# mainboard.net
KiCad netlist of a schematic drawn in EAGLE
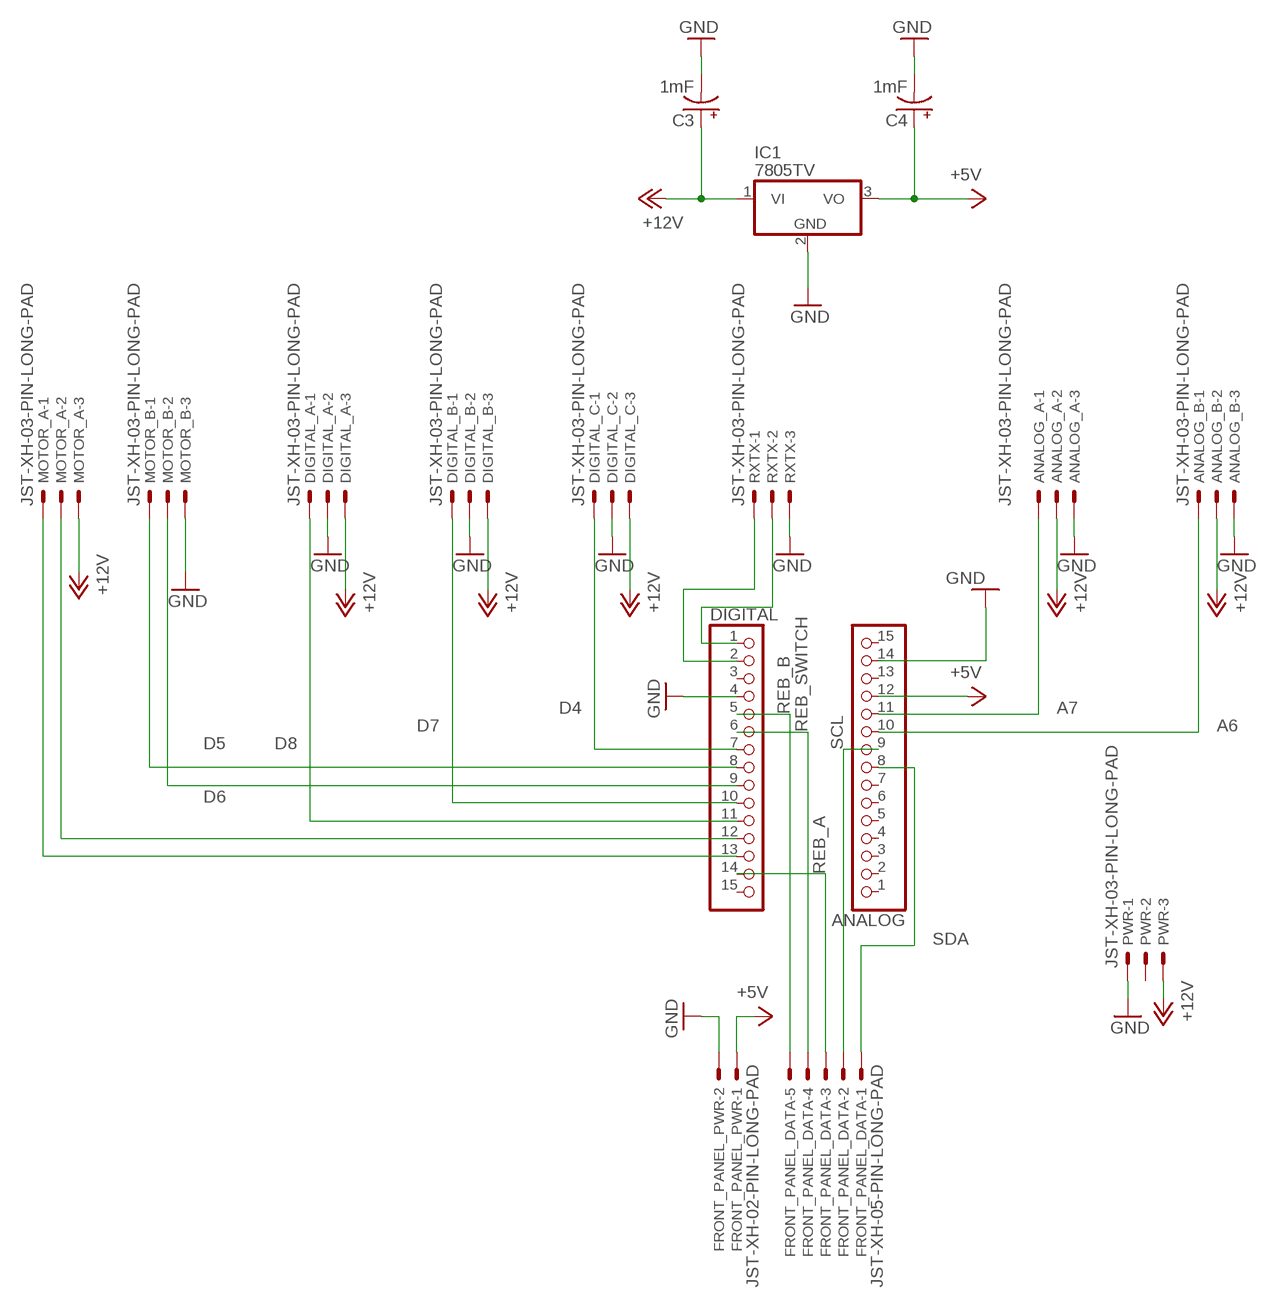
[diagram p0: schematic, sheet 1]

(export (version "E")
  (design (tool "Eeschema 10.0.6"))
  (components
    (comp (ref "ANALOG")
      (value "PINHD-1X15")
      (footprint "eagle-import:1X15")
      (libsource (lib "eagle-import") (part "PINHD-1X15"))
    )
    (comp (ref "ANALOG_A")
      (value "JST-XH-03-PIN-LONG-PAD")
      (footprint "eagle-import:JST-XH-03-PACKAGE-LONG-PAD")
      (libsource (lib "eagle-import") (part "JST-XH-03-PIN-LONG-PAD"))
    )
    (comp (ref "ANALOG_B")
      (value "JST-XH-03-PIN-LONG-PAD")
      (footprint "eagle-import:JST-XH-03-PACKAGE-LONG-PAD")
      (libsource (lib "eagle-import") (part "JST-XH-03-PIN-LONG-PAD"))
    )
    (comp (ref "C3")
      (value "1mF")
      (footprint "eagle-import:CPOL-RADIAL-5MM-10MM")
      (libsource (lib "eagle-import") (part "1000UF-RADIAL-5MM-25V-20%"))
    )
    (comp (ref "C4")
      (value "1mF")
      (footprint "eagle-import:CPOL-RADIAL-5MM-10MM")
      (libsource (lib "eagle-import") (part "1000UF-RADIAL-5MM-25V-20%"))
    )
    (comp (ref "DIGITAL")
      (value "PINHD-1X15")
      (footprint "eagle-import:1X15")
      (libsource (lib "eagle-import") (part "PINHD-1X15"))
    )
    (comp (ref "DIGITAL_A")
      (value "JST-XH-03-PIN-LONG-PAD")
      (footprint "eagle-import:JST-XH-03-PACKAGE-LONG-PAD")
      (libsource (lib "eagle-import") (part "JST-XH-03-PIN-LONG-PAD"))
    )
    (comp (ref "DIGITAL_B")
      (value "JST-XH-03-PIN-LONG-PAD")
      (footprint "eagle-import:JST-XH-03-PACKAGE-LONG-PAD")
      (libsource (lib "eagle-import") (part "JST-XH-03-PIN-LONG-PAD"))
    )
    (comp (ref "DIGITAL_C")
      (value "JST-XH-03-PIN-LONG-PAD")
      (footprint "eagle-import:JST-XH-03-PACKAGE-LONG-PAD")
      (libsource (lib "eagle-import") (part "JST-XH-03-PIN-LONG-PAD"))
    )
    (comp (ref "FRONT_PANEL_DATA")
      (value "JST-XH-05-PIN-LONG-PAD")
      (footprint "eagle-import:JST-XH-05-PACKAGE-LONG-PAD")
      (libsource (lib "eagle-import") (part "JST-XH-05-PIN-LONG-PAD"))
    )
    (comp (ref "FRONT_PANEL_PWR")
      (value "JST-XH-02-PIN-LONG-PAD")
      (footprint "eagle-import:JST-XH-02-PACKAGE-LONG-PAD")
      (libsource (lib "eagle-import") (part "JST-XH-02-PIN-LONG-PAD"))
    )
    (comp (ref "IC1")
      (value "7805TV")
      (footprint "eagle-import:TO220V")
      (libsource (lib "eagle-import") (part "78TV05"))
    )
    (comp (ref "MOTOR_A")
      (value "JST-XH-03-PIN-LONG-PAD")
      (footprint "eagle-import:JST-XH-03-PACKAGE-LONG-PAD")
      (libsource (lib "eagle-import") (part "JST-XH-03-PIN-LONG-PAD"))
    )
    (comp (ref "MOTOR_B")
      (value "JST-XH-03-PIN-LONG-PAD")
      (footprint "eagle-import:JST-XH-03-PACKAGE-LONG-PAD")
      (libsource (lib "eagle-import") (part "JST-XH-03-PIN-LONG-PAD"))
    )
    (comp (ref "PWR")
      (value "JST-XH-03-PIN-LONG-PAD")
      (footprint "eagle-import:JST-XH-03-PACKAGE-LONG-PAD")
      (libsource (lib "eagle-import") (part "JST-XH-03-PIN-LONG-PAD"))
    )
    (comp (ref "RXTX")
      (value "JST-XH-03-PIN-LONG-PAD")
      (footprint "eagle-import:JST-XH-03-PACKAGE-LONG-PAD")
      (libsource (lib "eagle-import") (part "JST-XH-03-PIN-LONG-PAD"))
    )
  )
  (nets
    (net (code "1") (name "+5V") (class "Default")
      (node (ref "ANALOG") (pin "12") (pinfunction "12_12") (pintype "passive"))
      (node (ref "C4") (pin "+") (pinfunction "+_+") (pintype "passive"))
      (node (ref "FRONT_PANEL_PWR") (pin "1") (pinfunction "S_1") (pintype "passive"))
      (node (ref "IC1") (pin "3") (pinfunction "VO_3") (pintype "passive"))
    )
    (net (code "2") (name "+12V") (class "Default")
      (node (ref "ANALOG_A") (pin "2") (pinfunction "S_2") (pintype "passive"))
      (node (ref "ANALOG_B") (pin "2") (pinfunction "S_2") (pintype "passive"))
      (node (ref "C3") (pin "+") (pinfunction "+_+") (pintype "passive"))
      (node (ref "DIGITAL_A") (pin "3") (pinfunction "S_3") (pintype "passive"))
      (node (ref "DIGITAL_B") (pin "3") (pinfunction "S_3") (pintype "passive"))
      (node (ref "DIGITAL_C") (pin "3") (pinfunction "S_3") (pintype "passive"))
      (node (ref "IC1") (pin "1") (pinfunction "VI_1") (pintype "input"))
      (node (ref "MOTOR_A") (pin "3") (pinfunction "S_3") (pintype "passive"))
      (node (ref "PWR") (pin "3") (pinfunction "S_3") (pintype "passive"))
    )
    (net (code "3") (name "/A6") (class "Default")
      (node (ref "ANALOG") (pin "10") (pinfunction "10_10") (pintype "passive"))
      (node (ref "ANALOG_B") (pin "1") (pinfunction "S_1") (pintype "passive"))
    )
    (net (code "4") (name "/A7") (class "Default")
      (node (ref "ANALOG") (pin "11") (pinfunction "11_11") (pintype "passive"))
      (node (ref "ANALOG_A") (pin "1") (pinfunction "S_1") (pintype "passive"))
    )
    (net (code "5") (name "/D4") (class "Default")
      (node (ref "DIGITAL") (pin "7") (pinfunction "7_7") (pintype "passive"))
      (node (ref "DIGITAL_C") (pin "1") (pinfunction "S_1") (pintype "passive"))
    )
    (net (code "6") (name "/D5") (class "Default")
      (node (ref "DIGITAL") (pin "8") (pinfunction "8_8") (pintype "passive"))
      (node (ref "MOTOR_B") (pin "1") (pinfunction "S_1") (pintype "passive"))
    )
    (net (code "7") (name "/D6") (class "Default")
      (node (ref "DIGITAL") (pin "9") (pinfunction "9_9") (pintype "passive"))
      (node (ref "MOTOR_B") (pin "2") (pinfunction "S_2") (pintype "passive"))
    )
    (net (code "8") (name "/D7") (class "Default")
      (node (ref "DIGITAL") (pin "10") (pinfunction "10_10") (pintype "passive"))
      (node (ref "DIGITAL_B") (pin "1") (pinfunction "S_1") (pintype "passive"))
    )
    (net (code "9") (name "/D8") (class "Default")
      (node (ref "DIGITAL") (pin "11") (pinfunction "11_11") (pintype "passive"))
      (node (ref "DIGITAL_A") (pin "1") (pinfunction "S_1") (pintype "passive"))
    )
    (net (code "10") (name "/REB_A") (class "Default")
      (node (ref "DIGITAL") (pin "14") (pinfunction "14_14") (pintype "passive"))
      (node (ref "FRONT_PANEL_DATA") (pin "3") (pinfunction "S_3") (pintype "passive"))
    )
    (net (code "11") (name "/REB_B") (class "Default")
      (node (ref "DIGITAL") (pin "5") (pinfunction "5_5") (pintype "passive"))
      (node (ref "FRONT_PANEL_DATA") (pin "5") (pinfunction "S_5") (pintype "passive"))
    )
    (net (code "12") (name "/REB_SWITCH") (class "Default")
      (node (ref "DIGITAL") (pin "6") (pinfunction "6_6") (pintype "passive"))
      (node (ref "FRONT_PANEL_DATA") (pin "4") (pinfunction "S_4") (pintype "passive"))
    )
    (net (code "13") (name "/SCL") (class "Default")
      (node (ref "ANALOG") (pin "9") (pinfunction "9_9") (pintype "passive"))
      (node (ref "FRONT_PANEL_DATA") (pin "2") (pinfunction "S_2") (pintype "passive"))
    )
    (net (code "14") (name "/SDA") (class "Default")
      (node (ref "ANALOG") (pin "8") (pinfunction "8_8") (pintype "passive"))
      (node (ref "FRONT_PANEL_DATA") (pin "1") (pinfunction "S_1") (pintype "passive"))
    )
    (net (code "15") (name "GND") (class "Default")
      (node (ref "ANALOG") (pin "14") (pinfunction "14_14") (pintype "passive"))
      (node (ref "ANALOG_A") (pin "3") (pinfunction "S_3") (pintype "passive"))
      (node (ref "ANALOG_B") (pin "3") (pinfunction "S_3") (pintype "passive"))
      (node (ref "C3") (pin "-") (pinfunction "-_-") (pintype "passive"))
      (node (ref "C4") (pin "-") (pinfunction "-_-") (pintype "passive"))
      (node (ref "DIGITAL") (pin "4") (pinfunction "4_4") (pintype "passive"))
      (node (ref "DIGITAL_A") (pin "2") (pinfunction "S_2") (pintype "passive"))
      (node (ref "DIGITAL_B") (pin "2") (pinfunction "S_2") (pintype "passive"))
      (node (ref "DIGITAL_C") (pin "2") (pinfunction "S_2") (pintype "passive"))
      (node (ref "FRONT_PANEL_PWR") (pin "2") (pinfunction "S_2") (pintype "passive"))
      (node (ref "IC1") (pin "2") (pinfunction "GND_2") (pintype "passive"))
      (node (ref "MOTOR_B") (pin "3") (pinfunction "S_3") (pintype "passive"))
      (node (ref "PWR") (pin "1") (pinfunction "S_1") (pintype "passive"))
      (node (ref "RXTX") (pin "3") (pinfunction "S_3") (pintype "passive"))
    )
    (net (code "16") (name "Net-(MOTOR_AA-S)") (class "Default")
      (node (ref "DIGITAL") (pin "13") (pinfunction "13_13") (pintype "passive"))
      (node (ref "MOTOR_A") (pin "1") (pinfunction "S_1") (pintype "passive"))
    )
    (net (code "17") (name "Net-(MOTOR_AB-S)") (class "Default")
      (node (ref "DIGITAL") (pin "12") (pinfunction "12_12") (pintype "passive"))
      (node (ref "MOTOR_A") (pin "2") (pinfunction "S_2") (pintype "passive"))
    )
    (net (code "18") (name "Net-(RXTXA-S)") (class "Default")
      (node (ref "DIGITAL") (pin "2") (pinfunction "2_2") (pintype "passive"))
      (node (ref "RXTX") (pin "1") (pinfunction "S_1") (pintype "passive"))
    )
    (net (code "19") (name "Net-(RXTXB-S)") (class "Default")
      (node (ref "DIGITAL") (pin "1") (pinfunction "1_1") (pintype "passive"))
      (node (ref "RXTX") (pin "2") (pinfunction "S_2") (pintype "passive"))
    )
    (net (code "20") (name "unconnected-(ANALOG-Pad1)") (class "Default")
      (node (ref "ANALOG") (pin "1") (pinfunction "1_1") (pintype "passive"))
    )
    (net (code "21") (name "unconnected-(ANALOG-Pad2)") (class "Default")
      (node (ref "ANALOG") (pin "2") (pinfunction "2_2") (pintype "passive"))
    )
    (net (code "22") (name "unconnected-(ANALOG-Pad3)") (class "Default")
      (node (ref "ANALOG") (pin "3") (pinfunction "3_3") (pintype "passive"))
    )
    (net (code "23") (name "unconnected-(ANALOG-Pad4)") (class "Default")
      (node (ref "ANALOG") (pin "4") (pinfunction "4_4") (pintype "passive"))
    )
    (net (code "24") (name "unconnected-(ANALOG-Pad5)") (class "Default")
      (node (ref "ANALOG") (pin "5") (pinfunction "5_5") (pintype "passive"))
    )
    (net (code "25") (name "unconnected-(ANALOG-Pad6)") (class "Default")
      (node (ref "ANALOG") (pin "6") (pinfunction "6_6") (pintype "passive"))
    )
    (net (code "26") (name "unconnected-(ANALOG-Pad7)") (class "Default")
      (node (ref "ANALOG") (pin "7") (pinfunction "7_7") (pintype "passive"))
    )
    (net (code "27") (name "unconnected-(ANALOG-Pad13)") (class "Default")
      (node (ref "ANALOG") (pin "13") (pinfunction "13_13") (pintype "passive"))
    )
    (net (code "28") (name "unconnected-(ANALOG-Pad15)") (class "Default")
      (node (ref "ANALOG") (pin "15") (pinfunction "15_15") (pintype "passive"))
    )
    (net (code "29") (name "unconnected-(DIGITAL-Pad3)") (class "Default")
      (node (ref "DIGITAL") (pin "3") (pinfunction "3_3") (pintype "passive"))
    )
    (net (code "30") (name "unconnected-(DIGITAL-Pad15)") (class "Default")
      (node (ref "DIGITAL") (pin "15") (pinfunction "15_15") (pintype "passive"))
    )
    (net (code "31") (name "unconnected-(PWRB-S-Pad2)") (class "Default")
      (node (ref "PWR") (pin "2") (pinfunction "S_2") (pintype "passive"))
    )
  )
)
